# 11-Transmitter.net
KiCad netlist of a schematic drawn in Altium Designer
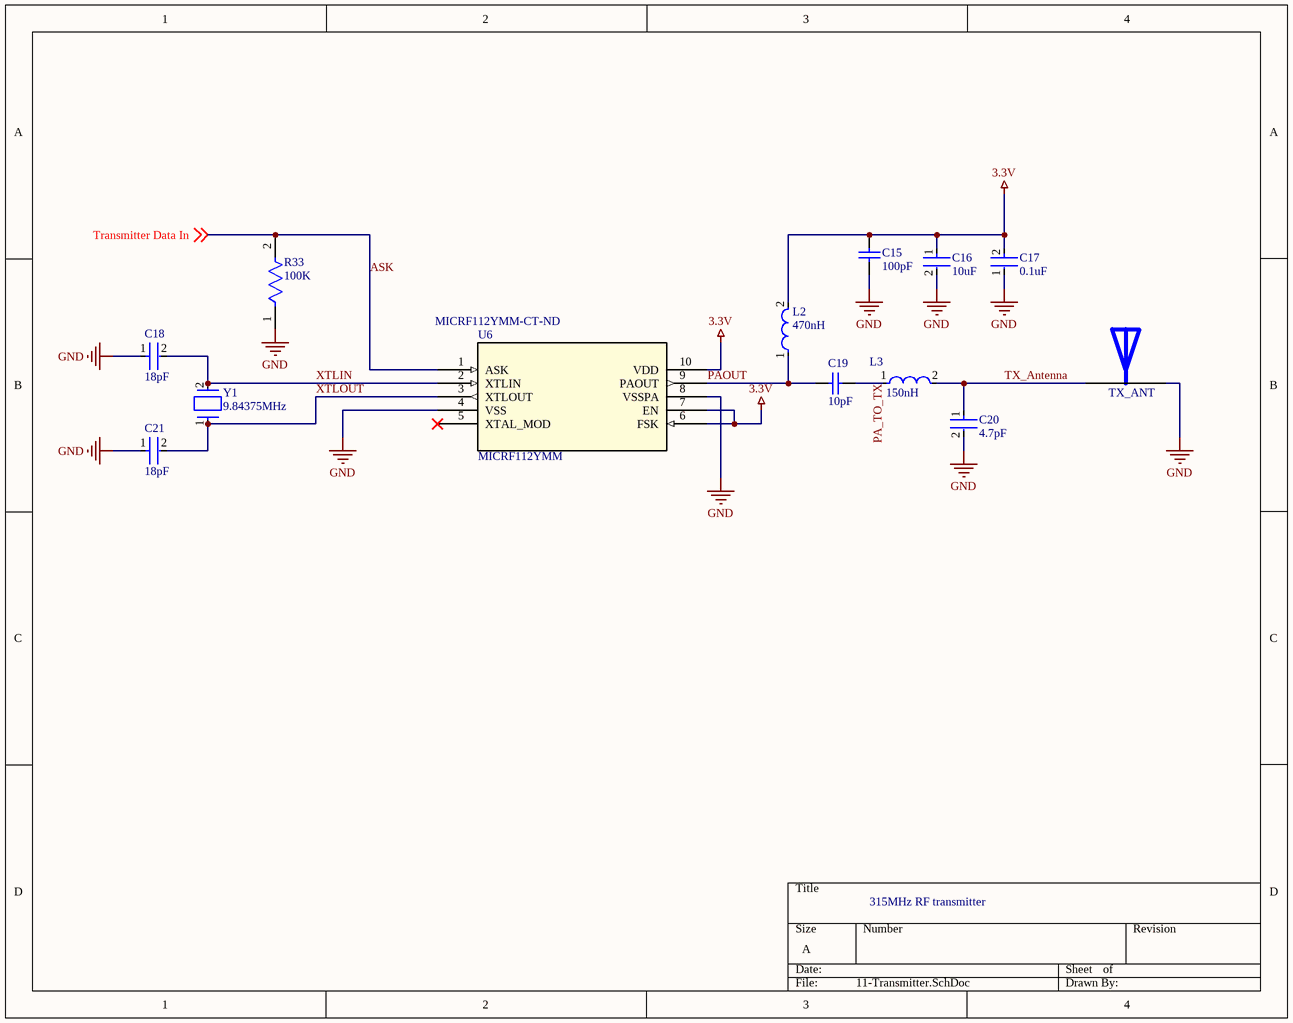
[diagram p0: 11-Transmitter.SchDoc]

(export (version "E")
  (design (tool "Eeschema 10.0.6"))
  (components
    (comp (ref "C15")
      (value "100pF")
      (footprint "CAPC1608X90X35NL10T15")
      (fields (field (name "PART NUMBER") "GRM1885C1H101JA01D") (field (name "MANUFACTURER") "Murata"))
      (libsource (lib "Altium Content Vault") (part "CAP"))
    )
    (comp (ref "C16")
      (value "10uF")
      (footprint "FP-GRM188-0_1-e0_2_0_55-IPC_A")
      (description "Chip Multilayer Ceramic Capacitors for General Purpose, 0603, 10uF, X5R, 15%, 20%, 6.3V")
      (fields (field (name "VOLTAGE") "6.3V") (field (name "TOLERANCE") "20%"))
      (libsource (lib "Altium Content Vault") (part "02cd4be3c70576c341d710602a673aa"))
    )
    (comp (ref "C17")
      (value "0.1uF")
      (footprint "FP-GRM15-MFG")
      (description "CAP CER 0.1UF 16V X7R 0402")
      (fields (field (name "MANUFACTURER PART NUMBER") "GRM155R71C104KA88D") (field (name "TOLERANCE") "10%"))
      (libsource (lib "Altium Content Vault") (part "236180d848d6139a670b325ea6854c9"))
    )
    (comp (ref "C18")
      (value "18pF")
      (footprint "FP-C0805C-DN-MFG")
      (description "CAP CER 18PF 50V C0G/NP0 0805")
      (fields
        (field (name "OCTOPART") "https://octopart.com/c0805c180j5gactu-kemet-144810")
        (field (name "TOLERANCE") "0.05")
      )
      (libsource (lib "Altium Content Vault") (part "b4654b650e69147ec39a6b967a45e02"))
    )
    (comp (ref "C19")
      (value "10pF")
      (footprint "CAPC1608X90X35LL10T15")
      (fields (field (name "PART NUMBER") "GRM1885C1H100JA01D") (field (name "MANUFACTURER") "Murata"))
      (libsource (lib "Altium Content Vault") (part "CAP"))
    )
    (comp (ref "C20")
      (value "4.7pF")
      (footprint "FP-C0402-BB-MFG")
      (description "CAP CER 4.7PF 50V NP0 0402")
      (fields
        (field (name "MANUFACTURER PART NUMBER") "C0402C479C5GACTU")
        (field (name "TOLERANCE") "0.25 pF")
      )
      (libsource (lib "Altium Content Vault") (part "b4654b650e69147ec39a6b967a45e02"))
    )
    (comp (ref "C21")
      (value "18pF")
      (footprint "FP-C0805C-DN-MFG")
      (description "CAP CER 18PF 50V C0G/NP0 0805")
      (fields
        (field (name "OCTOPART") "https://octopart.com/c0805c180j5gactu-kemet-144810")
        (field (name "TOLERANCE") "0.05")
      )
      (libsource (lib "Altium Content Vault") (part "b4654b650e69147ec39a6b967a45e02"))
    )
    (comp (ref "L2")
      (value "470nH")
      (footprint "FP-LQW2UAS_00-MFG")
      (description "Wire Wound RF Inductor 470nH ±5% 470mA 1.19Ω 1008 (2520)")
      (fields (field (name "TOLERANCE") "5%"))
      (libsource (lib "Altium Content Vault") (part "725321dda6339637d4d059423bc1c3c"))
    )
    (comp (ref "L3")
      (value "150nH")
      (footprint "FP-LQW2BHN_03-MFG")
      (description "Wire Wound RF Inductor 150nH ±5% 390mA 0.47Ω 0805 (2015)")
      (fields (field (name "TOLERANCE") "5%"))
      (libsource (lib "Altium Content Vault") (part "725321dda6339637d4d059423bc1c3c"))
    )
    (comp (ref "R33")
      (value "100K")
      (footprint "FP-ERJ2RK-IPC_C")
      (description "RES SMD 100K OHM 1% 1/10W 0402")
      (fields (field (name "TOLERANCE") "1%"))
      (libsource (lib "Altium Content Vault") (part "1029c3af85768c4190bb7ad29bc67b5"))
    )
    (comp (ref "TX_ANT")
      (value "TX Antenna")
      (footprint "TX_Antenna")
      (libsource (lib "team6") (part "TX Antenna"))
    )
    (comp (ref "U6")
      (value "MICRF112YMM")
      (footprint "MSOP10_MC_MCH")
      (description "No Description Available")
      (fields
        (field (name "SUPPLIER PART NUMBER 1") "MICRF112YMM-CT-ND")
        (field (name "COPYRIGHT") "Copyright (C) 2022 Ultra Librarian. All rights reserved.")
      )
      (libsource (lib "MICRF112YMM") (part "MICRF112YMM"))
    )
    (comp (ref "Y1")
      (value "9.84375MHz")
      (footprint "FP-ABM7-MFG")
      (description "Crystal 9.84375MHz ±30ppm 10pF SMD-2 6mm x 3.5mm")
      (libsource (lib "Altium Content Vault") (part "c23a69dc6c9e2f18f2079038eb95dd1"))
    )
  )
  (nets
    (net (code "1") (name "/PAOUT") (class "Default")
      (node (ref "C19") (pin "1") (pinfunction "1_1") (pintype "passive"))
      (node (ref "L2") (pin "1") (pinfunction "1_1") (pintype "passive"))
      (node (ref "U6") (pin "9") (pinfunction "PAOUT_9") (pintype "output"))
    )
    (net (code "2") (name "/PA_TO_TX") (class "Default")
      (node (ref "C19") (pin "2") (pinfunction "2_2") (pintype "passive"))
      (node (ref "L3") (pin "1") (pinfunction "1_1") (pintype "passive"))
    )
    (net (code "3") (name "/TX_Antenna") (class "Default")
      (node (ref "C20") (pin "1") (pinfunction "1_1") (pintype "passive"))
      (node (ref "L3") (pin "2") (pinfunction "2_2") (pintype "passive"))
      (node (ref "TX_ANT") (pin "1") (pinfunction "1_1") (pintype "passive"))
    )
    (net (code "4") (name "/XTLIN") (class "Default")
      (node (ref "C18") (pin "2") (pinfunction "2_2") (pintype "passive"))
      (node (ref "U6") (pin "2") (pinfunction "XTLIN_2") (pintype "input"))
      (node (ref "Y1") (pin "2") (pinfunction "2_2") (pintype "passive"))
    )
    (net (code "5") (name "/XTLOUT") (class "Default")
      (node (ref "C21") (pin "2") (pinfunction "2_2") (pintype "passive"))
      (node (ref "U6") (pin "3") (pinfunction "XTLOUT_3") (pintype "output"))
      (node (ref "Y1") (pin "1") (pinfunction "1_1") (pintype "passive"))
    )
    (net (code "6") (name "3.3V") (class "Default")
      (node (ref "C15") (pin "2") (pinfunction "2_2") (pintype "passive"))
      (node (ref "C16") (pin "1") (pinfunction "1_1") (pintype "passive"))
      (node (ref "C17") (pin "2") (pinfunction "2_2") (pintype "passive"))
      (node (ref "L2") (pin "2") (pinfunction "2_2") (pintype "passive"))
      (node (ref "U6") (pin "10") (pinfunction "VDD_10") (pintype "power_in"))
      (node (ref "U6") (pin "6") (pinfunction "FSK_6") (pintype "input"))
      (node (ref "U6") (pin "7") (pinfunction "EN_7") (pintype "passive"))
    )
    (net (code "7") (name "GND") (class "Default")
      (node (ref "C15") (pin "1") (pinfunction "1_1") (pintype "passive"))
      (node (ref "C16") (pin "2") (pinfunction "2_2") (pintype "passive"))
      (node (ref "C17") (pin "1") (pinfunction "1_1") (pintype "passive"))
      (node (ref "C18") (pin "1") (pinfunction "1_1") (pintype "passive"))
      (node (ref "C20") (pin "2") (pinfunction "2_2") (pintype "passive"))
      (node (ref "C21") (pin "1") (pinfunction "1_1") (pintype "passive"))
      (node (ref "R33") (pin "1") (pinfunction "1_1") (pintype "passive"))
      (node (ref "TX_ANT") (pin "2") (pinfunction "2_2") (pintype "passive"))
      (node (ref "U6") (pin "4") (pinfunction "VSS_4") (pintype "power_in"))
      (node (ref "U6") (pin "8") (pinfunction "VSSPA_8") (pintype "power_in"))
    )
    (net (code "8") (name "Transmitter Data In") (class "Default")
      (node (ref "R33") (pin "2") (pinfunction "2_2") (pintype "passive"))
      (node (ref "U6") (pin "1") (pinfunction "ASK_1") (pintype "input"))
    )
    (net (code "9") (name "unconnected-(U6-XTAL_MOD-Pad5)") (class "Default")
      (node (ref "U6") (pin "5") (pinfunction "XTAL_MOD_5") (pintype "passive+no_connect"))
    )
  )
)
